# design.net
KiCad netlist of a schematic drawn in Altium Designer
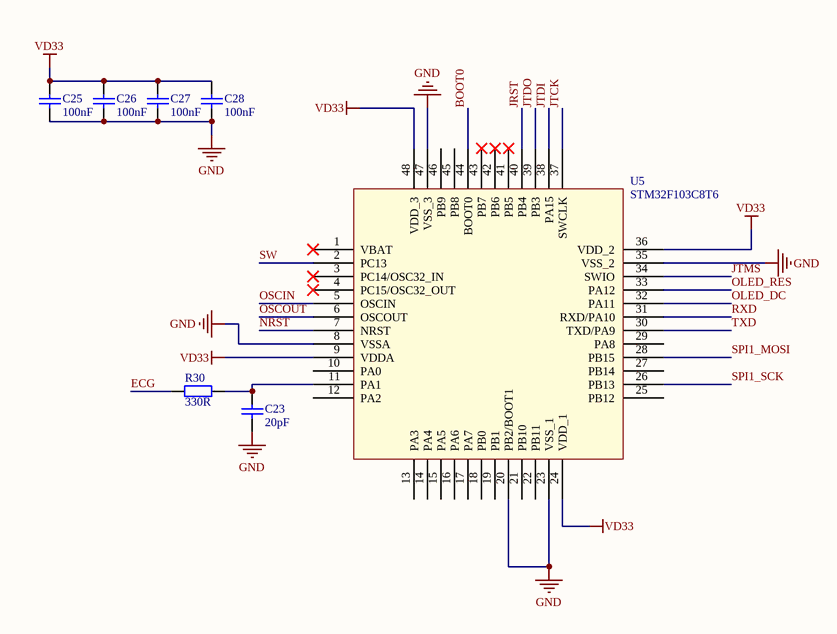
[diagram p0: 主控.SchDoc]

(export (version "E")
  (design (tool "Eeschema 10.0.6"))
  (components
    (comp (ref "C23")
      (value "20pF")
      (footprint "LC-0805_C")
      (description "100nF��0805��50V,+/-10%")
      (libsource (lib "ECG") (part "Cap"))
    )
    (comp (ref "C25")
      (value "100nF")
      (footprint "LC-0805_C")
      (description "100nF��0805��50V,+/-10%")
      (libsource (lib "ECG") (part "Cap"))
    )
    (comp (ref "C26")
      (value "100nF")
      (footprint "LC-0805_C")
      (description "100nF��0805��50V,+/-10%")
      (libsource (lib "ECG") (part "Cap"))
    )
    (comp (ref "C27")
      (value "100nF")
      (footprint "LC-0805_C")
      (description "100nF��0805��50V,+/-10%")
      (libsource (lib "ECG") (part "Cap"))
    )
    (comp (ref "C28")
      (value "100nF")
      (footprint "LC-0805_C")
      (description "100nF��0805��50V,+/-10%")
      (libsource (lib "ECG") (part "Cap"))
    )
    (comp (ref "R30")
      (value "330R")
      (footprint "LC-0805_R")
      (description "330��,0805,��5%")
      (libsource (lib "ECG") (part "Res1"))
    )
    (comp (ref "U5")
      (value "STM32F103C8T6")
      (footprint "LQFP48")
      (description "STM32F103C8T6,LQFP48")
      (libsource (lib "ECG") (part "STM32F103C8T6"))
    )
  )
  (nets
    (net (code "1") (name "/BOOT0") (class "Default")
      (node (ref "U5") (pin "44") (pinfunction "BOOT0_44") (pintype "open_collector"))
    )
    (net (code "2") (name "/ECG") (class "Default")
      (node (ref "R30") (pin "1") (pinfunction "1_1") (pintype "passive"))
    )
    (net (code "3") (name "/JRST") (class "Default")
      (node (ref "U5") (pin "40") (pinfunction "PB4_40") (pintype "open_collector"))
    )
    (net (code "4") (name "/JTCK") (class "Default")
      (node (ref "U5") (pin "37") (pinfunction "SWCLK_37") (pintype "open_collector"))
    )
    (net (code "5") (name "/JTDI") (class "Default")
      (node (ref "U5") (pin "38") (pinfunction "PA15_38") (pintype "open_collector"))
    )
    (net (code "6") (name "/JTDO") (class "Default")
      (node (ref "U5") (pin "39") (pinfunction "PB3_39") (pintype "open_collector"))
    )
    (net (code "7") (name "/JTMS") (class "Default")
      (node (ref "U5") (pin "34") (pinfunction "SWIO_34") (pintype "open_collector"))
    )
    (net (code "8") (name "/NRST") (class "Default")
      (node (ref "U5") (pin "7") (pinfunction "NRST_7") (pintype "open_collector"))
    )
    (net (code "9") (name "/OLED_DC") (class "Default")
      (node (ref "U5") (pin "32") (pinfunction "PA11_32") (pintype "open_collector"))
    )
    (net (code "10") (name "/OLED_RES") (class "Default")
      (node (ref "U5") (pin "33") (pinfunction "PA12_33") (pintype "open_collector"))
    )
    (net (code "11") (name "/OSCIN") (class "Default")
      (node (ref "U5") (pin "5") (pinfunction "OSCIN_5") (pintype "open_collector"))
    )
    (net (code "12") (name "/OSCOUT") (class "Default")
      (node (ref "U5") (pin "6") (pinfunction "OSCOUT_6") (pintype "open_collector"))
    )
    (net (code "13") (name "/RXD") (class "Default")
      (node (ref "U5") (pin "31") (pinfunction "RXD/PA10_31") (pintype "open_collector"))
    )
    (net (code "14") (name "/SPI1_MOSI") (class "Default")
      (node (ref "U5") (pin "28") (pinfunction "PB15_28") (pintype "open_collector"))
    )
    (net (code "15") (name "/SPI1_SCK") (class "Default")
      (node (ref "U5") (pin "26") (pinfunction "PB13_26") (pintype "open_collector"))
    )
    (net (code "16") (name "/SW") (class "Default")
      (node (ref "U5") (pin "2") (pinfunction "PC13_2") (pintype "open_collector"))
    )
    (net (code "17") (name "/TXD") (class "Default")
      (node (ref "U5") (pin "30") (pinfunction "TXD/PA9_30") (pintype "open_collector"))
    )
    (net (code "18") (name "GND") (class "Default")
      (node (ref "C23") (pin "2") (pinfunction "2_2") (pintype "passive"))
      (node (ref "C25") (pin "2") (pinfunction "2_2") (pintype "passive"))
      (node (ref "C26") (pin "2") (pinfunction "2_2") (pintype "passive"))
      (node (ref "C27") (pin "2") (pinfunction "2_2") (pintype "passive"))
      (node (ref "C28") (pin "2") (pinfunction "2_2") (pintype "passive"))
      (node (ref "U5") (pin "20") (pinfunction "PB2/BOOT1_20") (pintype "open_collector"))
      (node (ref "U5") (pin "23") (pinfunction "VSS_1_23") (pintype "open_collector"))
      (node (ref "U5") (pin "35") (pinfunction "VSS_2_35") (pintype "open_collector"))
      (node (ref "U5") (pin "47") (pinfunction "VSS_3_47") (pintype "open_collector"))
      (node (ref "U5") (pin "8") (pinfunction "VSSA_8") (pintype "open_collector"))
    )
    (net (code "19") (name "Net-(U5-PA1)") (class "Default")
      (node (ref "C23") (pin "1") (pinfunction "1_1") (pintype "passive"))
      (node (ref "R30") (pin "2") (pinfunction "2_2") (pintype "passive"))
      (node (ref "U5") (pin "11") (pinfunction "PA1_11") (pintype "open_collector"))
    )
    (net (code "20") (name "VD33") (class "Default")
      (node (ref "C25") (pin "1") (pinfunction "1_1") (pintype "passive"))
      (node (ref "C26") (pin "1") (pinfunction "1_1") (pintype "passive"))
      (node (ref "C27") (pin "1") (pinfunction "1_1") (pintype "passive"))
      (node (ref "C28") (pin "1") (pinfunction "1_1") (pintype "passive"))
      (node (ref "U5") (pin "24") (pinfunction "VDD_1_24") (pintype "open_collector"))
      (node (ref "U5") (pin "36") (pinfunction "VDD_2_36") (pintype "open_collector"))
      (node (ref "U5") (pin "48") (pinfunction "VDD_3_48") (pintype "open_collector"))
      (node (ref "U5") (pin "9") (pinfunction "VDDA_9") (pintype "open_collector"))
    )
    (net (code "21") (name "unconnected-(U5-PA0-Pad10)") (class "Default")
      (node (ref "U5") (pin "10") (pinfunction "PA0_10") (pintype "open_collector"))
    )
    (net (code "22") (name "unconnected-(U5-PA2-Pad12)") (class "Default")
      (node (ref "U5") (pin "12") (pinfunction "PA2_12") (pintype "open_collector"))
    )
    (net (code "23") (name "unconnected-(U5-PA3-Pad13)") (class "Default")
      (node (ref "U5") (pin "13") (pinfunction "PA3_13") (pintype "open_collector"))
    )
    (net (code "24") (name "unconnected-(U5-PA4-Pad14)") (class "Default")
      (node (ref "U5") (pin "14") (pinfunction "PA4_14") (pintype "open_collector"))
    )
    (net (code "25") (name "unconnected-(U5-PA5-Pad15)") (class "Default")
      (node (ref "U5") (pin "15") (pinfunction "PA5_15") (pintype "open_collector"))
    )
    (net (code "26") (name "unconnected-(U5-PA6-Pad16)") (class "Default")
      (node (ref "U5") (pin "16") (pinfunction "PA6_16") (pintype "open_collector"))
    )
    (net (code "27") (name "unconnected-(U5-PA7-Pad17)") (class "Default")
      (node (ref "U5") (pin "17") (pinfunction "PA7_17") (pintype "open_collector"))
    )
    (net (code "28") (name "unconnected-(U5-PA8-Pad29)") (class "Default")
      (node (ref "U5") (pin "29") (pinfunction "PA8_29") (pintype "open_collector"))
    )
    (net (code "29") (name "unconnected-(U5-PB0-Pad18)") (class "Default")
      (node (ref "U5") (pin "18") (pinfunction "PB0_18") (pintype "open_collector"))
    )
    (net (code "30") (name "unconnected-(U5-PB1-Pad19)") (class "Default")
      (node (ref "U5") (pin "19") (pinfunction "PB1_19") (pintype "open_collector"))
    )
    (net (code "31") (name "unconnected-(U5-PB5-Pad41)") (class "Default")
      (node (ref "U5") (pin "41") (pinfunction "PB5_41") (pintype "open_collector+no_connect"))
    )
    (net (code "32") (name "unconnected-(U5-PB6-Pad42)") (class "Default")
      (node (ref "U5") (pin "42") (pinfunction "PB6_42") (pintype "open_collector+no_connect"))
    )
    (net (code "33") (name "unconnected-(U5-PB7-Pad43)") (class "Default")
      (node (ref "U5") (pin "43") (pinfunction "PB7_43") (pintype "open_collector+no_connect"))
    )
    (net (code "34") (name "unconnected-(U5-PB8-Pad45)") (class "Default")
      (node (ref "U5") (pin "45") (pinfunction "PB8_45") (pintype "open_collector"))
    )
    (net (code "35") (name "unconnected-(U5-PB9-Pad46)") (class "Default")
      (node (ref "U5") (pin "46") (pinfunction "PB9_46") (pintype "open_collector"))
    )
    (net (code "36") (name "unconnected-(U5-PB10-Pad21)") (class "Default")
      (node (ref "U5") (pin "21") (pinfunction "PB10_21") (pintype "open_collector"))
    )
    (net (code "37") (name "unconnected-(U5-PB11-Pad22)") (class "Default")
      (node (ref "U5") (pin "22") (pinfunction "PB11_22") (pintype "open_collector"))
    )
    (net (code "38") (name "unconnected-(U5-PB12-Pad25)") (class "Default")
      (node (ref "U5") (pin "25") (pinfunction "PB12_25") (pintype "open_collector"))
    )
    (net (code "39") (name "unconnected-(U5-PB14-Pad27)") (class "Default")
      (node (ref "U5") (pin "27") (pinfunction "PB14_27") (pintype "open_collector"))
    )
    (net (code "40") (name "unconnected-(U5-PC14{slash}OSC32_IN-Pad3)") (class "Default")
      (node (ref "U5") (pin "3") (pinfunction "PC14/OSC32_IN_3") (pintype "open_collector+no_connect"))
    )
    (net (code "41") (name "unconnected-(U5-PC15{slash}OSC32_OUT-Pad4)") (class "Default")
      (node (ref "U5") (pin "4") (pinfunction "PC15/OSC32_OUT_4") (pintype "open_collector+no_connect"))
    )
    (net (code "42") (name "unconnected-(U5-VBAT-Pad1)") (class "Default")
      (node (ref "U5") (pin "1") (pinfunction "VBAT_1") (pintype "open_collector+no_connect"))
    )
  )
)
